# EVAL_USB4155.net
KiCad netlist of a schematic drawn in EAGLE
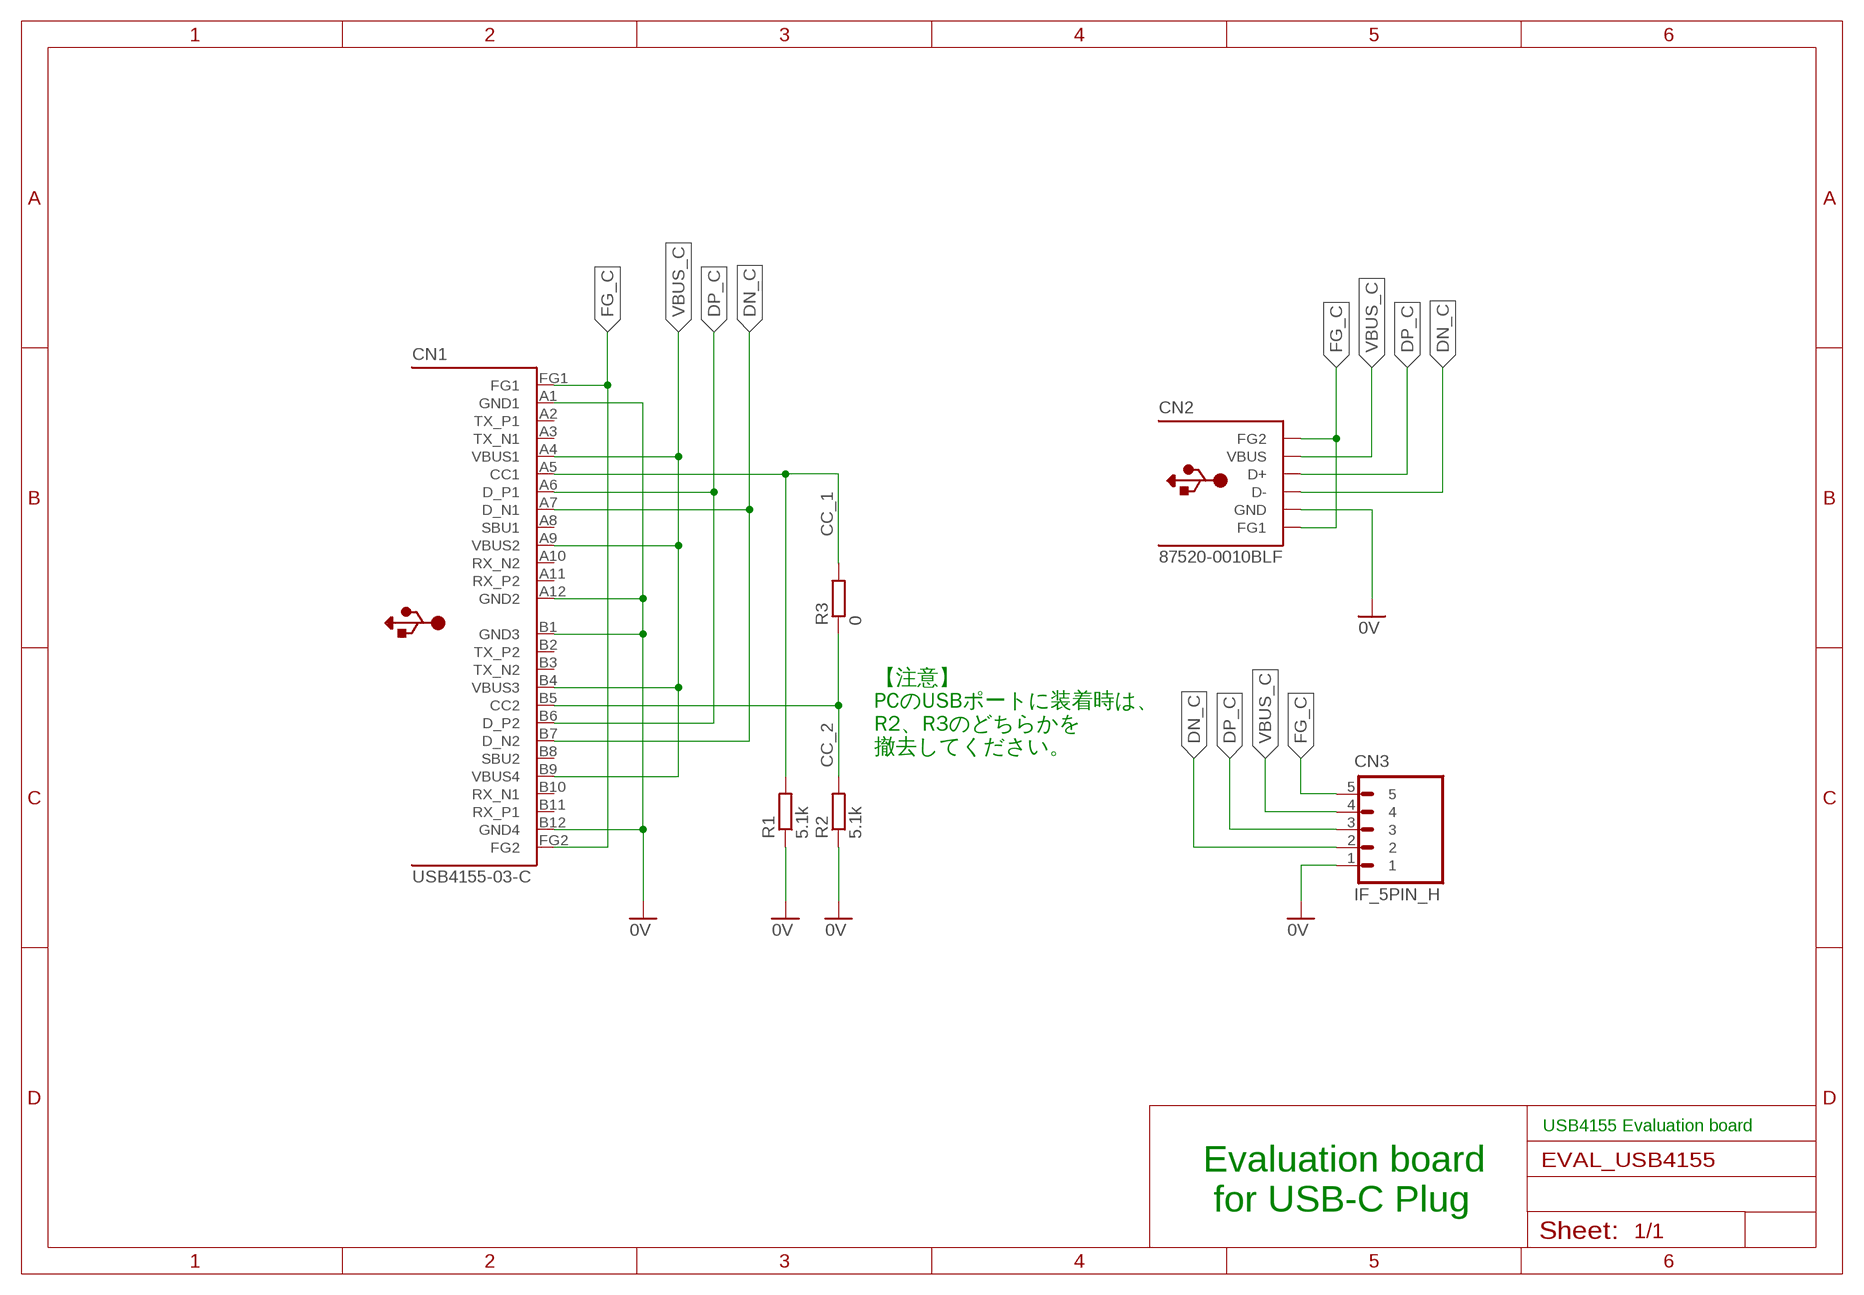
[diagram p0: schematic, sheet 1]

(export (version "E")
  (design (tool "Eeschema 10.0.6"))
  (components
    (comp (ref "CN1")
      (value "USB4155-03-C")
      (footprint "eagle-import:USB4155-03-C")
      (libsource (lib "eagle-import") (part "USB4155-03-C"))
    )
    (comp (ref "CN2")
      (value "87520-0010BLF")
      (footprint "eagle-import:87520-0010BLF")
      (libsource (lib "eagle-import") (part "87520-0010BLF"))
    )
    (comp (ref "CN3")
      (value "IF_5PIN_H")
      (footprint "eagle-import:HEADER_5PIN")
      (libsource (lib "eagle-import") (part "IF_5PIN_H"))
    )
    (comp (ref "R1")
      (value "5.1k")
      (footprint "eagle-import:R0402N")
      (libsource (lib "eagle-import") (part "RESISTOR_0402N"))
    )
    (comp (ref "R2")
      (value "5.1k")
      (footprint "eagle-import:R0402N")
      (libsource (lib "eagle-import") (part "RESISTOR_0402N"))
    )
    (comp (ref "R3")
      (value "0")
      (footprint "eagle-import:R0402N")
      (libsource (lib "eagle-import") (part "RESISTOR_0402N"))
    )
  )
  (nets
    (net (code "1") (name "/CC_1") (class "Default")
      (node (ref "CN1") (pin "A5") (pinfunction "CC1_A5") (pintype "passive"))
      (node (ref "R1") (pin "2") (pinfunction "2_2") (pintype "passive"))
      (node (ref "R3") (pin "2") (pinfunction "2_2") (pintype "passive"))
    )
    (net (code "2") (name "/CC_2") (class "Default")
      (node (ref "CN1") (pin "B5") (pinfunction "CC2_B5") (pintype "passive"))
      (node (ref "R2") (pin "2") (pinfunction "2_2") (pintype "passive"))
      (node (ref "R3") (pin "1") (pinfunction "1_1") (pintype "passive"))
    )
    (net (code "3") (name "0V") (class "Default")
      (node (ref "CN1") (pin "A1") (pinfunction "GND1_A1") (pintype "passive"))
      (node (ref "CN1") (pin "A12") (pinfunction "GND2_A12") (pintype "passive"))
      (node (ref "CN1") (pin "B1") (pinfunction "GND3_B1") (pintype "passive"))
      (node (ref "CN1") (pin "B12") (pinfunction "GND4_B12") (pintype "passive"))
      (node (ref "CN2") (pin "GND") (pinfunction "GND_GND") (pintype "passive"))
      (node (ref "CN3") (pin "1") (pinfunction "1_1") (pintype "passive"))
      (node (ref "R1") (pin "1") (pinfunction "1_1") (pintype "passive"))
      (node (ref "R2") (pin "1") (pinfunction "1_1") (pintype "passive"))
    )
    (net (code "4") (name "DN_C") (class "Default")
      (node (ref "CN1") (pin "A7") (pinfunction "D_N1_A7") (pintype "bidirectional"))
      (node (ref "CN1") (pin "B7") (pinfunction "D_N2_B7") (pintype "bidirectional"))
      (node (ref "CN2") (pin "D-") (pinfunction "D-_D-") (pintype "bidirectional"))
      (node (ref "CN3") (pin "2") (pinfunction "2_2") (pintype "passive"))
    )
    (net (code "5") (name "DP_C") (class "Default")
      (node (ref "CN1") (pin "A6") (pinfunction "D_P1_A6") (pintype "bidirectional"))
      (node (ref "CN1") (pin "B6") (pinfunction "D_P2_B6") (pintype "bidirectional"))
      (node (ref "CN2") (pin "D+") (pinfunction "D+_D+") (pintype "bidirectional"))
      (node (ref "CN3") (pin "3") (pinfunction "3_3") (pintype "passive"))
    )
    (net (code "6") (name "FG_C") (class "Default")
      (node (ref "CN1") (pin "FG1") (pinfunction "FG1_FG1") (pintype "passive"))
      (node (ref "CN1") (pin "FG2") (pinfunction "FG2_FG2") (pintype "bidirectional"))
      (node (ref "CN2") (pin "FG1") (pinfunction "FG1_FG1") (pintype "passive"))
      (node (ref "CN2") (pin "FG2") (pinfunction "FG2_FG2") (pintype "passive"))
      (node (ref "CN3") (pin "5") (pinfunction "5_5") (pintype "passive"))
    )
    (net (code "7") (name "VBUS_C") (class "Default")
      (node (ref "CN1") (pin "A4") (pinfunction "VBUS1_A4") (pintype "passive"))
      (node (ref "CN1") (pin "A9") (pinfunction "VBUS2_A9") (pintype "passive"))
      (node (ref "CN1") (pin "B4") (pinfunction "VBUS3_B4") (pintype "passive"))
      (node (ref "CN1") (pin "B9") (pinfunction "VBUS4_B9") (pintype "passive"))
      (node (ref "CN2") (pin "VBUS") (pinfunction "VBUS_VBUS") (pintype "passive"))
      (node (ref "CN3") (pin "4") (pinfunction "4_4") (pintype "passive"))
    )
    (net (code "8") (name "unconnected-(CN1-RX_N1-PadB10)") (class "Default")
      (node (ref "CN1") (pin "B10") (pinfunction "RX_N1_B10") (pintype "bidirectional"))
    )
    (net (code "9") (name "unconnected-(CN1-RX_N2-PadA10)") (class "Default")
      (node (ref "CN1") (pin "A10") (pinfunction "RX_N2_A10") (pintype "bidirectional"))
    )
    (net (code "10") (name "unconnected-(CN1-RX_P1-PadB11)") (class "Default")
      (node (ref "CN1") (pin "B11") (pinfunction "RX_P1_B11") (pintype "bidirectional"))
    )
    (net (code "11") (name "unconnected-(CN1-RX_P2-PadA11)") (class "Default")
      (node (ref "CN1") (pin "A11") (pinfunction "RX_P2_A11") (pintype "bidirectional"))
    )
    (net (code "12") (name "unconnected-(CN1-SBU1-PadA8)") (class "Default")
      (node (ref "CN1") (pin "A8") (pinfunction "SBU1_A8") (pintype "passive"))
    )
    (net (code "13") (name "unconnected-(CN1-SBU2-PadB8)") (class "Default")
      (node (ref "CN1") (pin "B8") (pinfunction "SBU2_B8") (pintype "passive"))
    )
    (net (code "14") (name "unconnected-(CN1-TX_N1-PadA3)") (class "Default")
      (node (ref "CN1") (pin "A3") (pinfunction "TX_N1_A3") (pintype "bidirectional"))
    )
    (net (code "15") (name "unconnected-(CN1-TX_N2-PadB3)") (class "Default")
      (node (ref "CN1") (pin "B3") (pinfunction "TX_N2_B3") (pintype "bidirectional"))
    )
    (net (code "16") (name "unconnected-(CN1-TX_P1-PadA2)") (class "Default")
      (node (ref "CN1") (pin "A2") (pinfunction "TX_P1_A2") (pintype "bidirectional"))
    )
    (net (code "17") (name "unconnected-(CN1-TX_P2-PadB2)") (class "Default")
      (node (ref "CN1") (pin "B2") (pinfunction "TX_P2_B2") (pintype "bidirectional"))
    )
  )
)
